# CPU.net
KiCad netlist of a schematic drawn in Altium Designer
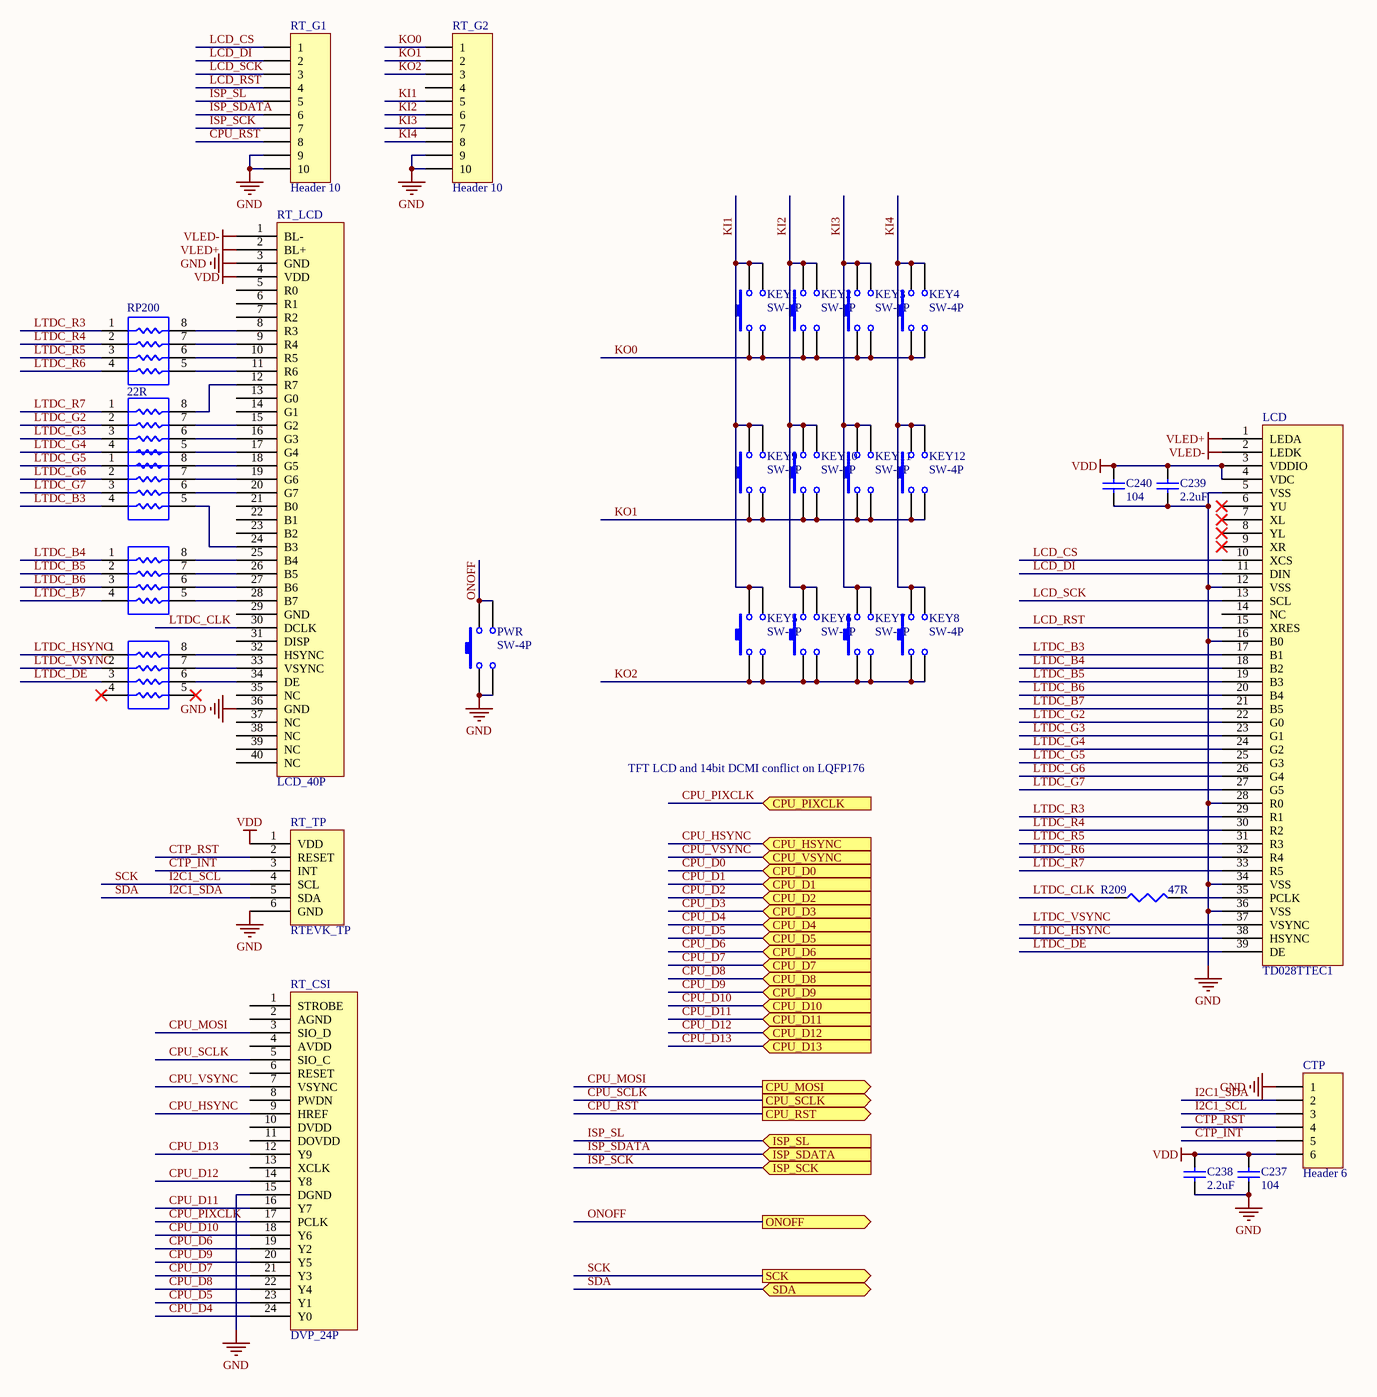
[diagram p0: CPU.SchDoc]

(export (version "E")
  (design (tool "Eeschema 10.0.6"))
  (components
    (comp (ref "C237")
      (value "104")
      (footprint "C0402")
      (description "Capacitor (Semiconductor SIM Model)")
      (fields (field (name "PUBLISHER") "Altium Limited"))
      (libsource (lib "Miscellaneous Devices") (part "Cap Semi"))
    )
    (comp (ref "C238")
      (value "2.2uF")
      (footprint "C0603")
      (description "Capacitor (Semiconductor SIM Model)")
      (fields (field (name "PUBLISHER") "Altium Limited"))
      (libsource (lib "Miscellaneous Devices") (part "Cap Semi"))
    )
    (comp (ref "C239")
      (value "2.2uF")
      (footprint "C0603")
      (description "Capacitor (Semiconductor SIM Model)")
      (fields (field (name "PUBLISHER") "Altium Limited"))
      (libsource (lib "Miscellaneous Devices") (part "Cap Semi"))
    )
    (comp (ref "C240")
      (value "104")
      (footprint "C0402")
      (description "Capacitor (Semiconductor SIM Model)")
      (fields (field (name "PUBLISHER") "Altium Limited"))
      (libsource (lib "Miscellaneous Devices") (part "Cap Semi"))
    )
    (comp (ref "CTP")
      (value "Header 6")
      (footprint "CTP")
      (description "Header, 6-Pin")
      (fields (field (name "PUBLISHER") "Altium Limited"))
      (libsource (lib "Miscellaneous Connectors") (part "Header 6"))
    )
    (comp (ref "KEY1")
      (value "SW-4P")
      (footprint "KEY-4P")
      (description "Switch")
      (fields (field (name "PUBLISHER") "Altium Limited"))
      (libsource (lib "Schlib1") (part "SW-4P"))
    )
    (comp (ref "KEY2")
      (value "SW-4P")
      (footprint "KEY-4P")
      (description "Switch")
      (fields (field (name "PUBLISHER") "Altium Limited"))
      (libsource (lib "Schlib1") (part "SW-4P"))
    )
    (comp (ref "KEY3")
      (value "SW-4P")
      (footprint "KEY-4P")
      (description "Switch")
      (fields (field (name "PUBLISHER") "Altium Limited"))
      (libsource (lib "Schlib1") (part "SW-4P"))
    )
    (comp (ref "KEY4")
      (value "SW-4P")
      (footprint "KEY-4P")
      (description "Switch")
      (fields (field (name "PUBLISHER") "Altium Limited"))
      (libsource (lib "Schlib1") (part "SW-4P"))
    )
    (comp (ref "KEY5")
      (value "SW-4P")
      (footprint "KEY-4P")
      (description "Switch")
      (fields (field (name "PUBLISHER") "Altium Limited"))
      (libsource (lib "Schlib1") (part "SW-4P"))
    )
    (comp (ref "KEY6")
      (value "SW-4P")
      (footprint "KEY-4P")
      (description "Switch")
      (fields (field (name "PUBLISHER") "Altium Limited"))
      (libsource (lib "Schlib1") (part "SW-4P"))
    )
    (comp (ref "KEY7")
      (value "SW-4P")
      (footprint "KEY-4P")
      (description "Switch")
      (fields (field (name "PUBLISHER") "Altium Limited"))
      (libsource (lib "Schlib1") (part "SW-4P"))
    )
    (comp (ref "KEY8")
      (value "SW-4P")
      (footprint "KEY-4P")
      (description "Switch")
      (fields (field (name "PUBLISHER") "Altium Limited"))
      (libsource (lib "Schlib1") (part "SW-4P"))
    )
    (comp (ref "KEY9")
      (value "SW-4P")
      (footprint "KEY-4P")
      (description "Switch")
      (fields (field (name "PUBLISHER") "Altium Limited"))
      (libsource (lib "Schlib1") (part "SW-4P"))
    )
    (comp (ref "KEY10")
      (value "SW-4P")
      (footprint "KEY-4P")
      (description "Switch")
      (fields (field (name "PUBLISHER") "Altium Limited"))
      (libsource (lib "Schlib1") (part "SW-4P"))
    )
    (comp (ref "KEY11")
      (value "SW-4P")
      (footprint "KEY-4P")
      (description "Switch")
      (fields (field (name "PUBLISHER") "Altium Limited"))
      (libsource (lib "Schlib1") (part "SW-4P"))
    )
    (comp (ref "KEY12")
      (value "SW-4P")
      (footprint "KEY-4P")
      (description "Switch")
      (fields (field (name "PUBLISHER") "Altium Limited"))
      (libsource (lib "Schlib1") (part "SW-4P"))
    )
    (comp (ref "LCD")
      (value "TD028TTEC1")
      (footprint "FPC_39")
      (libsource (lib "Schlib1") (part "TD028TTEC1"))
    )
    (comp (ref "PWR")
      (value "SW-4P")
      (footprint "KEY-4P")
      (description "Switch")
      (fields (field (name "PUBLISHER") "Altium Limited"))
      (libsource (lib "Schlib1") (part "SW-4P"))
    )
    (comp (ref "R209")
      (value "47R")
      (footprint "R0603")
      (description "Resistor")
      (fields (field (name "PUBLISHER") "Altium Limited"))
      (libsource (lib "Miscellaneous Devices") (part "Res3"))
    )
    (comp (ref "RP200")
      (value "22R")
      (footprint "R0402S4")
      (description "Isolated Resistor Network")
      (fields (field (name "PUBLISHER") "Altium Limited"))
      (libsource (lib "Schlib1") (part "ResPack"))
    )
    (comp (ref "RP201")
      (value "22R")
      (footprint "R0402S4")
      (description "Isolated Resistor Network")
      (fields (field (name "PUBLISHER") "Altium Limited"))
      (libsource (lib "Schlib1") (part "ResPack"))
    )
    (comp (ref "RP202")
      (value "22R")
      (footprint "R0402S4")
      (description "Isolated Resistor Network")
      (fields (field (name "PUBLISHER") "Altium Limited"))
      (libsource (lib "Schlib1") (part "ResPack"))
    )
    (comp (ref "RP203")
      (value "22R")
      (footprint "R0402S4")
      (description "Isolated Resistor Network")
      (fields (field (name "PUBLISHER") "Altium Limited"))
      (libsource (lib "Schlib1") (part "ResPack"))
    )
    (comp (ref "RP204")
      (value "22R")
      (footprint "R0402S4")
      (description "Isolated Resistor Network")
      (fields (field (name "PUBLISHER") "Altium Limited"))
      (libsource (lib "Schlib1") (part "ResPack"))
    )
    (comp (ref "RT_CSI")
      (value "DVP_24P")
      (footprint "24PIN-0.5MM")
      (libsource (lib "Schlib1") (part "DVP_24P"))
    )
    (comp (ref "RT_G1")
      (value "Header 10")
      (footprint "HEADER10")
      (description "Header, 10-Pin")
      (fields (field (name "PUBLISHER") "Altium Limited"))
      (libsource (lib "Miscellaneous Connectors") (part "Header 10"))
    )
    (comp (ref "RT_G2")
      (value "Header 10")
      (footprint "HEADER10")
      (description "Header, 10-Pin")
      (fields (field (name "PUBLISHER") "Altium Limited"))
      (libsource (lib "Miscellaneous Connectors") (part "Header 10"))
    )
    (comp (ref "RT_LCD")
      (value "LCD_40P")
      (footprint "40PIN-0.5MM")
      (libsource (lib "Schlib1") (part "LCD_40P"))
    )
    (comp (ref "RT_TP") (value "RTEVK_TP") (footprint "CTP") (libsource (lib "Schlib1") (part "RTEVK_TP")))
  )
  (nets
    (net (code "5") (name "/CPU_D4") (class "Default")
      (node (ref "RT_CSI") (pin "24") (pinfunction "Y0_24") (pintype "passive"))
    )
    (net (code "6") (name "/CPU_D5") (class "Default")
      (node (ref "RT_CSI") (pin "23") (pinfunction "Y1_23") (pintype "passive"))
    )
    (net (code "7") (name "/CPU_D6") (class "Default")
      (node (ref "RT_CSI") (pin "19") (pinfunction "Y2_19") (pintype "passive"))
    )
    (net (code "8") (name "/CPU_D7") (class "Default")
      (node (ref "RT_CSI") (pin "21") (pinfunction "Y3_21") (pintype "passive"))
    )
    (net (code "9") (name "/CPU_D8") (class "Default")
      (node (ref "RT_CSI") (pin "22") (pinfunction "Y4_22") (pintype "passive"))
    )
    (net (code "10") (name "/CPU_D9") (class "Default")
      (node (ref "RT_CSI") (pin "20") (pinfunction "Y5_20") (pintype "passive"))
    )
    (net (code "11") (name "/CPU_D10") (class "Default")
      (node (ref "RT_CSI") (pin "18") (pinfunction "Y6_18") (pintype "passive"))
    )
    (net (code "12") (name "/CPU_D11") (class "Default")
      (node (ref "RT_CSI") (pin "16") (pinfunction "Y7_16") (pintype "passive"))
    )
    (net (code "13") (name "/CPU_D12") (class "Default")
      (node (ref "RT_CSI") (pin "14") (pinfunction "Y8_14") (pintype "passive"))
    )
    (net (code "14") (name "/CPU_D13") (class "Default")
      (node (ref "RT_CSI") (pin "12") (pinfunction "Y9_12") (pintype "passive"))
    )
    (net (code "15") (name "/CPU_HSYNC") (class "Default")
      (node (ref "RT_CSI") (pin "9") (pinfunction "HREF_9") (pintype "passive"))
    )
    (net (code "16") (name "/CPU_MOSI") (class "Default")
      (node (ref "RT_CSI") (pin "3") (pinfunction "SIO_D_3") (pintype "passive"))
    )
    (net (code "17") (name "/CPU_PIXCLK") (class "Default")
      (node (ref "RT_CSI") (pin "17") (pinfunction "PCLK_17") (pintype "passive"))
    )
    (net (code "18") (name "/CPU_RST") (class "Default")
      (node (ref "RT_G1") (pin "8") (pinfunction "8_8") (pintype "passive"))
    )
    (net (code "19") (name "/CPU_SCLK") (class "Default")
      (node (ref "RT_CSI") (pin "5") (pinfunction "SIO_C_5") (pintype "passive"))
    )
    (net (code "20") (name "/CPU_VSYNC") (class "Default")
      (node (ref "RT_CSI") (pin "7") (pinfunction "VSYNC_7") (pintype "passive"))
    )
    (net (code "21") (name "/CTP_INT") (class "Default")
      (node (ref "CTP") (pin "5") (pinfunction "5_5") (pintype "passive"))
      (node (ref "RT_TP") (pin "3") (pinfunction "INT_3") (pintype "passive"))
    )
    (net (code "22") (name "/CTP_RST") (class "Default")
      (node (ref "CTP") (pin "4") (pinfunction "4_4") (pintype "passive"))
      (node (ref "RT_TP") (pin "2") (pinfunction "RESET_2") (pintype "passive"))
    )
    (net (code "23") (name "/I2C1_SCL") (class "Default")
      (node (ref "CTP") (pin "3") (pinfunction "3_3") (pintype "passive"))
      (node (ref "RT_TP") (pin "4") (pinfunction "SCL_4") (pintype "passive"))
    )
    (net (code "24") (name "/I2C1_SDA") (class "Default")
      (node (ref "CTP") (pin "2") (pinfunction "2_2") (pintype "passive"))
      (node (ref "RT_TP") (pin "5") (pinfunction "SDA_5") (pintype "passive"))
    )
    (net (code "25") (name "/ISP_SCK") (class "Default")
      (node (ref "RT_G1") (pin "7") (pinfunction "7_7") (pintype "passive"))
    )
    (net (code "26") (name "/ISP_SDATA") (class "Default")
      (node (ref "RT_G1") (pin "6") (pinfunction "6_6") (pintype "passive"))
    )
    (net (code "27") (name "/ISP_SL") (class "Default")
      (node (ref "RT_G1") (pin "5") (pinfunction "5_5") (pintype "passive"))
    )
    (net (code "28") (name "/KI1") (class "Default")
      (node (ref "KEY1") (pin "2") (pinfunction "2_2") (pintype "passive"))
      (node (ref "KEY1") (pin "4") (pinfunction "4_4") (pintype "passive"))
      (node (ref "KEY5") (pin "2") (pinfunction "2_2") (pintype "passive"))
      (node (ref "KEY5") (pin "4") (pinfunction "4_4") (pintype "passive"))
      (node (ref "KEY9") (pin "2") (pinfunction "2_2") (pintype "passive"))
      (node (ref "KEY9") (pin "4") (pinfunction "4_4") (pintype "passive"))
      (node (ref "RT_G2") (pin "5") (pinfunction "5_5") (pintype "passive"))
    )
    (net (code "29") (name "/KI2") (class "Default")
      (node (ref "KEY10") (pin "2") (pinfunction "2_2") (pintype "passive"))
      (node (ref "KEY10") (pin "4") (pinfunction "4_4") (pintype "passive"))
      (node (ref "KEY2") (pin "2") (pinfunction "2_2") (pintype "passive"))
      (node (ref "KEY2") (pin "4") (pinfunction "4_4") (pintype "passive"))
      (node (ref "KEY6") (pin "2") (pinfunction "2_2") (pintype "passive"))
      (node (ref "KEY6") (pin "4") (pinfunction "4_4") (pintype "passive"))
      (node (ref "RT_G2") (pin "6") (pinfunction "6_6") (pintype "passive"))
    )
    (net (code "30") (name "/KI3") (class "Default")
      (node (ref "KEY11") (pin "2") (pinfunction "2_2") (pintype "passive"))
      (node (ref "KEY11") (pin "4") (pinfunction "4_4") (pintype "passive"))
      (node (ref "KEY3") (pin "2") (pinfunction "2_2") (pintype "passive"))
      (node (ref "KEY3") (pin "4") (pinfunction "4_4") (pintype "passive"))
      (node (ref "KEY7") (pin "2") (pinfunction "2_2") (pintype "passive"))
      (node (ref "KEY7") (pin "4") (pinfunction "4_4") (pintype "passive"))
      (node (ref "RT_G2") (pin "7") (pinfunction "7_7") (pintype "passive"))
    )
    (net (code "31") (name "/KI4") (class "Default")
      (node (ref "KEY12") (pin "2") (pinfunction "2_2") (pintype "passive"))
      (node (ref "KEY12") (pin "4") (pinfunction "4_4") (pintype "passive"))
      (node (ref "KEY4") (pin "2") (pinfunction "2_2") (pintype "passive"))
      (node (ref "KEY4") (pin "4") (pinfunction "4_4") (pintype "passive"))
      (node (ref "KEY8") (pin "2") (pinfunction "2_2") (pintype "passive"))
      (node (ref "KEY8") (pin "4") (pinfunction "4_4") (pintype "passive"))
      (node (ref "RT_G2") (pin "8") (pinfunction "8_8") (pintype "passive"))
    )
    (net (code "32") (name "/KO0") (class "Default")
      (node (ref "KEY1") (pin "1") (pinfunction "1_1") (pintype "passive"))
      (node (ref "KEY1") (pin "3") (pinfunction "3_3") (pintype "passive"))
      (node (ref "KEY2") (pin "1") (pinfunction "1_1") (pintype "passive"))
      (node (ref "KEY2") (pin "3") (pinfunction "3_3") (pintype "passive"))
      (node (ref "KEY3") (pin "1") (pinfunction "1_1") (pintype "passive"))
      (node (ref "KEY3") (pin "3") (pinfunction "3_3") (pintype "passive"))
      (node (ref "KEY4") (pin "1") (pinfunction "1_1") (pintype "passive"))
      (node (ref "KEY4") (pin "3") (pinfunction "3_3") (pintype "passive"))
      (node (ref "RT_G2") (pin "1") (pinfunction "1_1") (pintype "passive"))
    )
    (net (code "33") (name "/KO1") (class "Default")
      (node (ref "KEY10") (pin "1") (pinfunction "1_1") (pintype "passive"))
      (node (ref "KEY10") (pin "3") (pinfunction "3_3") (pintype "passive"))
      (node (ref "KEY11") (pin "1") (pinfunction "1_1") (pintype "passive"))
      (node (ref "KEY11") (pin "3") (pinfunction "3_3") (pintype "passive"))
      (node (ref "KEY12") (pin "1") (pinfunction "1_1") (pintype "passive"))
      (node (ref "KEY12") (pin "3") (pinfunction "3_3") (pintype "passive"))
      (node (ref "KEY9") (pin "1") (pinfunction "1_1") (pintype "passive"))
      (node (ref "KEY9") (pin "3") (pinfunction "3_3") (pintype "passive"))
      (node (ref "RT_G2") (pin "2") (pinfunction "2_2") (pintype "passive"))
    )
    (net (code "34") (name "/KO2") (class "Default")
      (node (ref "KEY5") (pin "1") (pinfunction "1_1") (pintype "passive"))
      (node (ref "KEY5") (pin "3") (pinfunction "3_3") (pintype "passive"))
      (node (ref "KEY6") (pin "1") (pinfunction "1_1") (pintype "passive"))
      (node (ref "KEY6") (pin "3") (pinfunction "3_3") (pintype "passive"))
      (node (ref "KEY7") (pin "1") (pinfunction "1_1") (pintype "passive"))
      (node (ref "KEY7") (pin "3") (pinfunction "3_3") (pintype "passive"))
      (node (ref "KEY8") (pin "1") (pinfunction "1_1") (pintype "passive"))
      (node (ref "KEY8") (pin "3") (pinfunction "3_3") (pintype "passive"))
      (node (ref "RT_G2") (pin "3") (pinfunction "3_3") (pintype "passive"))
    )
    (net (code "35") (name "/LCD_CS") (class "Default")
      (node (ref "LCD") (pin "10") (pinfunction "XCS_10") (pintype "passive"))
      (node (ref "RT_G1") (pin "1") (pinfunction "1_1") (pintype "passive"))
    )
    (net (code "36") (name "/LCD_DI") (class "Default")
      (node (ref "LCD") (pin "11") (pinfunction "DIN_11") (pintype "passive"))
      (node (ref "RT_G1") (pin "2") (pinfunction "2_2") (pintype "passive"))
    )
    (net (code "37") (name "/LCD_RST") (class "Default")
      (node (ref "LCD") (pin "15") (pinfunction "XRES_15") (pintype "passive"))
      (node (ref "RT_G1") (pin "4") (pinfunction "4_4") (pintype "passive"))
    )
    (net (code "38") (name "/LCD_SCK") (class "Default")
      (node (ref "LCD") (pin "13") (pinfunction "SCL_13") (pintype "passive"))
      (node (ref "RT_G1") (pin "3") (pinfunction "3_3") (pintype "passive"))
    )
    (net (code "39") (name "/LTDC_B3") (class "Default")
      (node (ref "LCD") (pin "17") (pinfunction "B1_17") (pintype "passive"))
      (node (ref "RP202") (pin "4") (pinfunction "4_4") (pintype "passive"))
    )
    (net (code "40") (name "/LTDC_B4") (class "Default")
      (node (ref "LCD") (pin "18") (pinfunction "B2_18") (pintype "passive"))
      (node (ref "RP203") (pin "1") (pinfunction "1_1") (pintype "passive"))
    )
    (net (code "41") (name "/LTDC_B5") (class "Default")
      (node (ref "LCD") (pin "19") (pinfunction "B3_19") (pintype "passive"))
      (node (ref "RP203") (pin "2") (pinfunction "2_2") (pintype "passive"))
    )
    (net (code "42") (name "/LTDC_B6") (class "Default")
      (node (ref "LCD") (pin "20") (pinfunction "B4_20") (pintype "passive"))
      (node (ref "RP203") (pin "3") (pinfunction "3_3") (pintype "passive"))
    )
    (net (code "43") (name "/LTDC_B7") (class "Default")
      (node (ref "LCD") (pin "21") (pinfunction "B5_21") (pintype "passive"))
      (node (ref "RP203") (pin "4") (pinfunction "4_4") (pintype "passive"))
    )
    (net (code "44") (name "/LTDC_CLK") (class "Default")
      (node (ref "R209") (pin "1") (pinfunction "1_1") (pintype "passive"))
      (node (ref "RT_LCD") (pin "30") (pinfunction "DCLK_30") (pintype "passive"))
    )
    (net (code "45") (name "/LTDC_DE") (class "Default")
      (node (ref "LCD") (pin "39") (pinfunction "DE_39") (pintype "passive"))
      (node (ref "RP204") (pin "3") (pinfunction "3_3") (pintype "passive"))
    )
    (net (code "46") (name "/LTDC_G2") (class "Default")
      (node (ref "LCD") (pin "22") (pinfunction "G0_22") (pintype "passive"))
      (node (ref "RP201") (pin "2") (pinfunction "2_2") (pintype "passive"))
    )
    (net (code "47") (name "/LTDC_G3") (class "Default")
      (node (ref "LCD") (pin "23") (pinfunction "G1_23") (pintype "passive"))
      (node (ref "RP201") (pin "3") (pinfunction "3_3") (pintype "passive"))
    )
    (net (code "48") (name "/LTDC_G4") (class "Default")
      (node (ref "LCD") (pin "24") (pinfunction "G2_24") (pintype "passive"))
      (node (ref "RP201") (pin "4") (pinfunction "4_4") (pintype "passive"))
    )
    (net (code "49") (name "/LTDC_G5") (class "Default")
      (node (ref "LCD") (pin "25") (pinfunction "G3_25") (pintype "passive"))
      (node (ref "RP202") (pin "1") (pinfunction "1_1") (pintype "passive"))
    )
    (net (code "50") (name "/LTDC_G6") (class "Default")
      (node (ref "LCD") (pin "26") (pinfunction "G4_26") (pintype "passive"))
      (node (ref "RP202") (pin "2") (pinfunction "2_2") (pintype "passive"))
    )
    (net (code "51") (name "/LTDC_G7") (class "Default")
      (node (ref "LCD") (pin "27") (pinfunction "G5_27") (pintype "passive"))
      (node (ref "RP202") (pin "3") (pinfunction "3_3") (pintype "passive"))
    )
    (net (code "52") (name "/LTDC_HSYNC") (class "Default")
      (node (ref "LCD") (pin "38") (pinfunction "HSYNC_38") (pintype "passive"))
      (node (ref "RP204") (pin "1") (pinfunction "1_1") (pintype "passive"))
    )
    (net (code "53") (name "/LTDC_R3") (class "Default")
      (node (ref "LCD") (pin "29") (pinfunction "R1_29") (pintype "passive"))
      (node (ref "RP200") (pin "1") (pinfunction "1_1") (pintype "passive"))
    )
    (net (code "54") (name "/LTDC_R4") (class "Default")
      (node (ref "LCD") (pin "30") (pinfunction "R2_30") (pintype "passive"))
      (node (ref "RP200") (pin "2") (pinfunction "2_2") (pintype "passive"))
    )
    (net (code "55") (name "/LTDC_R5") (class "Default")
      (node (ref "LCD") (pin "31") (pinfunction "R3_31") (pintype "passive"))
      (node (ref "RP200") (pin "3") (pinfunction "3_3") (pintype "passive"))
    )
    (net (code "56") (name "/LTDC_R6") (class "Default")
      (node (ref "LCD") (pin "32") (pinfunction "R4_32") (pintype "passive"))
      (node (ref "RP200") (pin "4") (pinfunction "4_4") (pintype "passive"))
    )
    (net (code "57") (name "/LTDC_R7") (class "Default")
      (node (ref "LCD") (pin "33") (pinfunction "R5_33") (pintype "passive"))
      (node (ref "RP201") (pin "1") (pinfunction "1_1") (pintype "passive"))
    )
    (net (code "58") (name "/LTDC_VSYNC") (class "Default")
      (node (ref "LCD") (pin "37") (pinfunction "VSYNC_37") (pintype "passive"))
      (node (ref "RP204") (pin "2") (pinfunction "2_2") (pintype "passive"))
    )
    (net (code "59") (name "/ONOFF") (class "Default")
      (node (ref "PWR") (pin "2") (pinfunction "2_2") (pintype "passive"))
      (node (ref "PWR") (pin "4") (pinfunction "4_4") (pintype "passive"))
    )
    (net (code "60") (name "GND") (class "Default")
      (node (ref "C237") (pin "1") (pinfunction "1_1") (pintype "passive"))
      (node (ref "C238") (pin "1") (pinfunction "1_1") (pintype "passive"))
      (node (ref "C239") (pin "1") (pinfunction "1_1") (pintype "passive"))
      (node (ref "C240") (pin "1") (pinfunction "1_1") (pintype "passive"))
      (node (ref "CTP") (pin "1") (pinfunction "1_1") (pintype "passive"))
      (node (ref "LCD") (pin "12") (pinfunction "VSS_12") (pintype "passive"))
      (node (ref "LCD") (pin "16") (pinfunction "B0_16") (pintype "passive"))
      (node (ref "LCD") (pin "28") (pinfunction "R0_28") (pintype "passive"))
      (node (ref "LCD") (pin "34") (pinfunction "VSS_34") (pintype "passive"))
      (node (ref "LCD") (pin "36") (pinfunction "VSS_36") (pintype "passive"))
      (node (ref "LCD") (pin "5") (pinfunction "VSS_5") (pintype "passive"))
      (node (ref "PWR") (pin "1") (pinfunction "1_1") (pintype "passive"))
      (node (ref "PWR") (pin "3") (pinfunction "3_3") (pintype "passive"))
      (node (ref "RT_CSI") (pin "15") (pinfunction "DGND_15") (pintype "passive"))
      (node (ref "RT_G1") (pin "10") (pinfunction "10_10") (pintype "passive"))
      (node (ref "RT_G1") (pin "9") (pinfunction "9_9") (pintype "passive"))
      (node (ref "RT_G2") (pin "10") (pinfunction "10_10") (pintype "passive"))
      (node (ref "RT_G2") (pin "9") (pinfunction "9_9") (pintype "passive"))
      (node (ref "RT_LCD") (pin "3") (pinfunction "GND_3") (pintype "passive"))
      (node (ref "RT_LCD") (pin "36") (pinfunction "GND_36") (pintype "passive"))
      (node (ref "RT_TP") (pin "6") (pinfunction "GND_6") (pintype "passive"))
    )
    (net (code "61") (name "Net-(LCD-PCLK)") (class "Default")
      (node (ref "LCD") (pin "35") (pinfunction "PCLK_35") (pintype "passive"))
      (node (ref "R209") (pin "2") (pinfunction "2_2") (pintype "passive"))
    )
    (net (code "62") (name "Net-(RT_LCD-B3)") (class "Default")
      (node (ref "RP202") (pin "5") (pinfunction "5_5") (pintype "passive"))
      (node (ref "RT_LCD") (pin "24") (pinfunction "B3_24") (pintype "passive"))
    )
    (net (code "63") (name "Net-(RT_LCD-B4)") (class "Default")
      (node (ref "RP203") (pin "8") (pinfunction "8_8") (pintype "passive"))
      (node (ref "RT_LCD") (pin "25") (pinfunction "B4_25") (pintype "passive"))
    )
    (net (code "64") (name "Net-(RT_LCD-B5)") (class "Default")
      (node (ref "RP203") (pin "7") (pinfunction "7_7") (pintype "passive"))
      (node (ref "RT_LCD") (pin "26") (pinfunction "B5_26") (pintype "passive"))
    )
    (net (code "65") (name "Net-(RT_LCD-B6)") (class "Default")
      (node (ref "RP203") (pin "6") (pinfunction "6_6") (pintype "passive"))
      (node (ref "RT_LCD") (pin "27") (pinfunction "B6_27") (pintype "passive"))
    )
    (net (code "66") (name "Net-(RT_LCD-B7)") (class "Default")
      (node (ref "RP203") (pin "5") (pinfunction "5_5") (pintype "passive"))
      (node (ref "RT_LCD") (pin "28") (pinfunction "B7_28") (pintype "passive"))
    )
    (net (code "67") (name "Net-(RT_LCD-DE)") (class "Default")
      (node (ref "RP204") (pin "6") (pinfunction "6_6") (pintype "passive"))
      (node (ref "RT_LCD") (pin "34") (pinfunction "DE_34") (pintype "passive"))
    )
    (net (code "68") (name "Net-(RT_LCD-G2)") (class "Default")
      (node (ref "RP201") (pin "7") (pinfunction "7_7") (pintype "passive"))
      (node (ref "RT_LCD") (pin "15") (pinfunction "G2_15") (pintype "passive"))
    )
    (net (code "69") (name "Net-(RT_LCD-G3)") (class "Default")
      (node (ref "RP201") (pin "6") (pinfunction "6_6") (pintype "passive"))
      (node (ref "RT_LCD") (pin "16") (pinfunction "G3_16") (pintype "passive"))
    )
    (net (code "70") (name "Net-(RT_LCD-G4)") (class "Default")
      (node (ref "RP201") (pin "5") (pinfunction "5_5") (pintype "passive"))
      (node (ref "RT_LCD") (pin "17") (pinfunction "G4_17") (pintype "passive"))
    )
    (net (code "71") (name "Net-(RT_LCD-G5)") (class "Default")
      (node (ref "RP202") (pin "8") (pinfunction "8_8") (pintype "passive"))
      (node (ref "RT_LCD") (pin "18") (pinfunction "G5_18") (pintype "passive"))
    )
    (net (code "72") (name "Net-(RT_LCD-G6)") (class "Default")
      (node (ref "RP202") (pin "7") (pinfunction "7_7") (pintype "passive"))
      (node (ref "RT_LCD") (pin "19") (pinfunction "G6_19") (pintype "passive"))
    )
    (net (code "73") (name "Net-(RT_LCD-G7)") (class "Default")
      (node (ref "RP202") (pin "6") (pinfunction "6_6") (pintype "passive"))
      (node (ref "RT_LCD") (pin "20") (pinfunction "G7_20") (pintype "passive"))
    )
    (net (code "74") (name "Net-(RT_LCD-HSYNC)") (class "Default")
      (node (ref "RP204") (pin "8") (pinfunction "8_8") (pintype "passive"))
      (node (ref "RT_LCD") (pin "32") (pinfunction "HSYNC_32") (pintype "passive"))
    )
    (net (code "75") (name "Net-(RT_LCD-R3)") (class "Default")
      (node (ref "RP200") (pin "8") (pinfunction "8_8") (pintype "passive"))
      (node (ref "RT_LCD") (pin "8") (pinfunction "R3_8") (pintype "passive"))
    )
    (net (code "76") (name "Net-(RT_LCD-R4)") (class "Default")
      (node (ref "RP200") (pin "7") (pinfunction "7_7") (pintype "passive"))
      (node (ref "RT_LCD") (pin "9") (pinfunction "R4_9") (pintype "passive"))
    )
    (net (code "77") (name "Net-(RT_LCD-R5)") (class "Default")
      (node (ref "RP200") (pin "6") (pinfunction "6_6") (pintype "passive"))
      (node (ref "RT_LCD") (pin "10") (pinfunction "R5_10") (pintype "passive"))
    )
    (net (code "78") (name "Net-(RT_LCD-R6)") (class "Default")
      (node (ref "RP200") (pin "5") (pinfunction "5_5") (pintype "passive"))
      (node (ref "RT_LCD") (pin "11") (pinfunction "R6_11") (pintype "passive"))
    )
    (net (code "79") (name "Net-(RT_LCD-R7)") (class "Default")
      (node (ref "RP201") (pin "8") (pinfunction "8_8") (pintype "passive"))
      (node (ref "RT_LCD") (pin "12") (pinfunction "R7_12") (pintype "passive"))
    )
    (net (code "80") (name "Net-(RT_LCD-VSYNC)") (class "Default")
      (node (ref "RP204") (pin "7") (pinfunction "7_7") (pintype "passive"))
      (node (ref "RT_LCD") (pin "33") (pinfunction "VSYNC_33") (pintype "passive"))
    )
    (net (code "81") (name "VDD") (class "Default")
      (node (ref "C237") (pin "2") (pinfunction "2_2") (pintype "passive"))
      (node (ref "C238") (pin "2") (pinfunction "2_2") (pintype "passive"))
      (node (ref "C239") (pin "2") (pinfunction "2_2") (pintype "passive"))
      (node (ref "C240") (pin "2") (pinfunction "2_2") (pintype "passive"))
      (node (ref "CTP") (pin "6") (pinfunction "6_6") (pintype "passive"))
      (node (ref "LCD") (pin "3") (pinfunction "VDDIO_3") (pintype "passive"))
      (node (ref "LCD") (pin "4") (pinfunction "VDC_4") (pintype "passive"))
      (node (ref "RT_LCD") (pin "4") (pinfunction "VDD_4") (pintype "passive"))
      (node (ref "RT_TP") (pin "1") (pinfunction "VDD_1") (pintype "passive"))
    )
    (net (code "82") (name "VLED+") (class "Default")
      (node (ref "LCD") (pin "1") (pinfunction "LEDA_1") (pintype "passive"))
      (node (ref "RT_LCD") (pin "2") (pinfunction "BL+_2") (pintype "passive"))
    )
    (net (code "83") (name "VLED-") (class "Default")
      (node (ref "LCD") (pin "2") (pinfunction "LEDK_2") (pintype "passive"))
      (node (ref "RT_LCD") (pin "1") (pinfunction "BL-_1") (pintype "passive"))
    )
    (net (code "84") (name "unconnected-(LCD-NC-Pad14)") (class "Default")
      (node (ref "LCD") (pin "14") (pinfunction "NC_14") (pintype "passive"))
    )
    (net (code "85") (name "unconnected-(LCD-XL-Pad7)") (class "Default")
      (node (ref "LCD") (pin "7") (pinfunction "XL_7") (pintype "passive+no_connect"))
    )
    (net (code "86") (name "unconnected-(LCD-XR-Pad9)") (class "Default")
      (node (ref "LCD") (pin "9") (pinfunction "XR_9") (pintype "passive+no_connect"))
    )
    (net (code "87") (name "unconnected-(LCD-YL-Pad8)") (class "Default")
      (node (ref "LCD") (pin "8") (pinfunction "YL_8") (pintype "passive+no_connect"))
    )
    (net (code "88") (name "unconnected-(LCD-YU-Pad6)") (class "Default")
      (node (ref "LCD") (pin "6") (pinfunction "YU_6") (pintype "passive+no_connect"))
    )
    (net (code "89") (name "unconnected-(RP204-Pad4)") (class "Default")
      (node (ref "RP204") (pin "4") (pinfunction "4_4") (pintype "passive+no_connect"))
    )
    (net (code "90") (name "unconnected-(RP204-Pad5)") (class "Default")
      (node (ref "RP204") (pin "5") (pinfunction "5_5") (pintype "passive+no_connect"))
    )
    (net (code "91") (name "unconnected-(RT_CSI-AGND-Pad2)") (class "Default")
      (node (ref "RT_CSI") (pin "2") (pinfunction "AGND_2") (pintype "passive"))
    )
    (net (code "92") (name "unconnected-(RT_CSI-AVDD-Pad4)") (class "Default")
      (node (ref "RT_CSI") (pin "4") (pinfunction "AVDD_4") (pintype "passive"))
    )
    (net (code "93") (name "unconnected-(RT_CSI-DOVDD-Pad11)") (class "Default")
      (node (ref "RT_CSI") (pin "11") (pinfunction "DOVDD_11") (pintype "passive"))
    )
    (net (code "94") (name "unconnected-(RT_CSI-DVDD-Pad10)") (class "Default")
      (node (ref "RT_CSI") (pin "10") (pinfunction "DVDD_10") (pintype "passive"))
    )
    (net (code "95") (name "unconnected-(RT_CSI-PWDN-Pad8)") (class "Default")
      (node (ref "RT_CSI") (pin "8") (pinfunction "PWDN_8") (pintype "passive"))
    )
    (net (code "96") (name "unconnected-(RT_CSI-RESET-Pad6)") (class "Default")
      (node (ref "RT_CSI") (pin "6") (pinfunction "RESET_6") (pintype "passive"))
    )
    (net (code "97") (name "unconnected-(RT_CSI-STROBE-Pad1)") (class "Default")
      (node (ref "RT_CSI") (pin "1") (pinfunction "STROBE_1") (pintype "passive"))
    )
    (net (code "98") (name "unconnected-(RT_CSI-XCLK-Pad13)") (class "Default")
      (node (ref "RT_CSI") (pin "13") (pinfunction "XCLK_13") (pintype "passive"))
    )
    (net (code "99") (name "unconnected-(RT_G2-Pad4)") (class "Default")
      (node (ref "RT_G2") (pin "4") (pinfunction "4_4") (pintype "passive"))
    )
    (net (code "100") (name "unconnected-(RT_LCD-B0-Pad21)") (class "Default")
      (node (ref "RT_LCD") (pin "21") (pinfunction "B0_21") (pintype "passive"))
    )
    (net (code "101") (name "unconnected-(RT_LCD-B1-Pad22)") (class "Default")
      (node (ref "RT_LCD") (pin "22") (pinfunction "B1_22") (pintype "passive"))
    )
    (net (code "102") (name "unconnected-(RT_LCD-B2-Pad23)") (class "Default")
      (node (ref "RT_LCD") (pin "23") (pinfunction "B2_23") (pintype "passive"))
    )
    (net (code "103") (name "unconnected-(RT_LCD-DISP-Pad31)") (class "Default")
      (node (ref "RT_LCD") (pin "31") (pinfunction "DISP_31") (pintype "passive"))
    )
    (net (code "104") (name "unconnected-(RT_LCD-G0-Pad13)") (class "Default")
      (node (ref "RT_LCD") (pin "13") (pinfunction "G0_13") (pintype "passive"))
    )
    (net (code "105") (name "unconnected-(RT_LCD-G1-Pad14)") (class "Default")
      (node (ref "RT_LCD") (pin "14") (pinfunction "G1_14") (pintype "passive"))
    )
    (net (code "106") (name "unconnected-(RT_LCD-GND-Pad29)") (class "Default")
      (node (ref "RT_LCD") (pin "29") (pinfunction "GND_29") (pintype "passive"))
    )
    (net (code "107") (name "unconnected-(RT_LCD-NC-Pad35)") (class "Default")
      (node (ref "RT_LCD") (pin "35") (pinfunction "NC_35") (pintype "passive"))
    )
    (net (code "108") (name "unconnected-(RT_LCD-NC-Pad37)") (class "Default")
      (node (ref "RT_LCD") (pin "37") (pinfunction "NC_37") (pintype "passive"))
    )
    (net (code "109") (name "unconnected-(RT_LCD-NC-Pad38)") (class "Default")
      (node (ref "RT_LCD") (pin "38") (pinfunction "NC_38") (pintype "passive"))
    )
    (net (code "110") (name "unconnected-(RT_LCD-NC-Pad39)") (class "Default")
      (node (ref "RT_LCD") (pin "39") (pinfunction "NC_39") (pintype "passive"))
    )
    (net (code "111") (name "unconnected-(RT_LCD-NC-Pad40)") (class "Default")
      (node (ref "RT_LCD") (pin "40") (pinfunction "NC_40") (pintype "passive"))
    )
    (net (code "112") (name "unconnected-(RT_LCD-R0-Pad5)") (class "Default")
      (node (ref "RT_LCD") (pin "5") (pinfunction "R0_5") (pintype "passive"))
    )
    (net (code "113") (name "unconnected-(RT_LCD-R1-Pad6)") (class "Default")
      (node (ref "RT_LCD") (pin "6") (pinfunction "R1_6") (pintype "passive"))
    )
    (net (code "114") (name "unconnected-(RT_LCD-R2-Pad7)") (class "Default")
      (node (ref "RT_LCD") (pin "7") (pinfunction "R2_7") (pintype "passive"))
    )
  )
)
